# 05_CPU03.net
KiCad netlist of a schematic drawn in Altium Designer
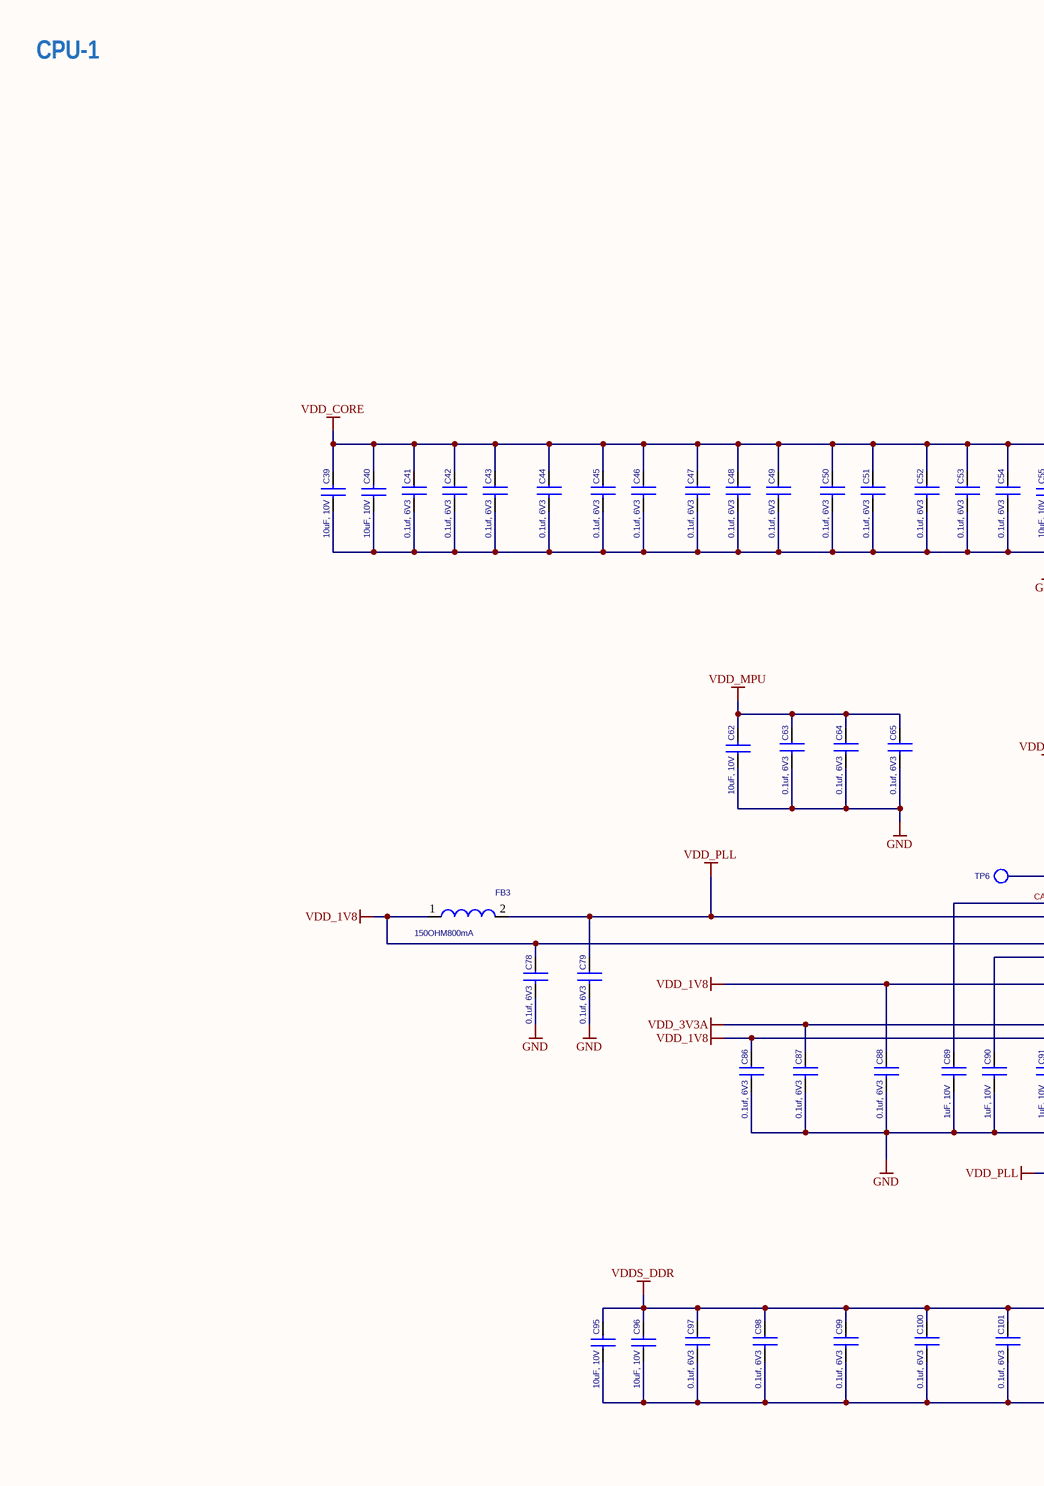
[diagram p0: 05_CPU03.SchDoc, left]
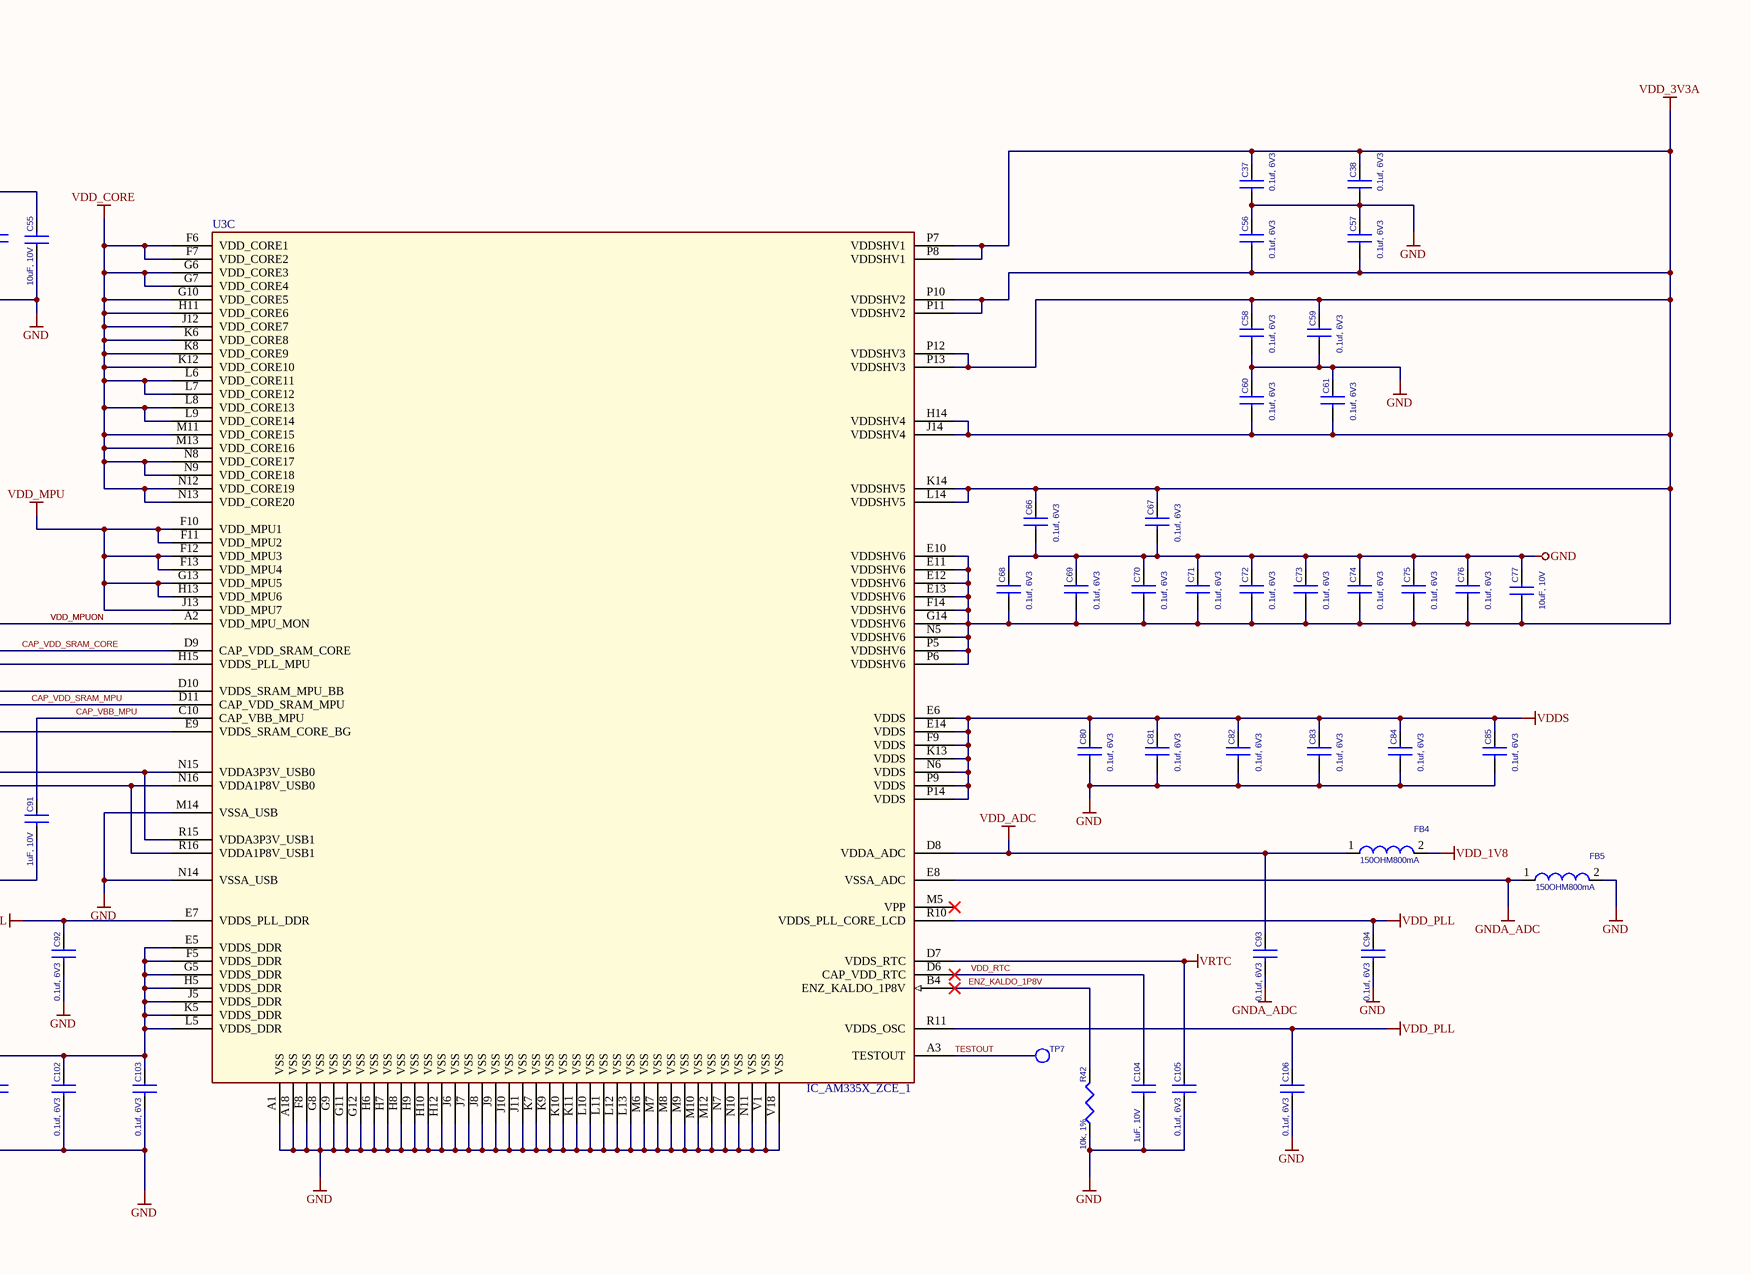
[diagram p1: 05_CPU03.SchDoc, right]

(export (version "E")
  (design (tool "Eeschema 10.0.6"))
  (components
    (comp (ref "C37")
      (value "0.1uf, 6V3")
      (footprint "402")
      (description "CAP CER 0.1UF 6.3V 10% X5R 0402")
      (fields
        (field (name "MANUFACTURER") "TDK Corporation")
        (field (name "MANUFACTURER PART NUMBER") "C1005X5R0J104K050BA")
      )
      (libsource (lib "BEAGLEBONEBLACK_REV A5B") (part "CAP_0.1uF_X7R_16V_10% 0402"))
    )
    (comp (ref "C38")
      (value "0.1uf, 6V3")
      (footprint "402")
      (description "CAP CER 0.1UF 6.3V 10% X5R 0402")
      (fields
        (field (name "MANUFACTURER") "TDK Corporation")
        (field (name "MANUFACTURER PART NUMBER") "C1005X5R0J104K050BA")
      )
      (libsource (lib "BEAGLEBONEBLACK_REV A5B") (part "CAP_0.1uF_X7R_16V_10% 0402"))
    )
    (comp (ref "C39")
      (value "10uF, 10V")
      (description "CAP CER 10UF 10V Y5V 0805")
      (fields
        (field (name "MANUFACTURER") "TDK Corporation")
        (field (name "MANUFACTURER PART NUMBER") "C2012Y5V1A106Z")
      )
      (libsource (lib "BEAGLEBONEBLACK_REV A5B") (part "CAP_10uF_Y5V_10V_10%_0805"))
    )
    (comp (ref "C40")
      (value "10uF, 10V")
      (description "CAP CER 10UF 10V Y5V 0805")
      (fields
        (field (name "MANUFACTURER") "TDK Corporation")
        (field (name "MANUFACTURER PART NUMBER") "C2012Y5V1A106Z")
      )
      (libsource (lib "BEAGLEBONEBLACK_REV A5B") (part "CAP_10uF_Y5V_10V_10%_0805"))
    )
    (comp (ref "C41")
      (value "0.1uf, 6V3")
      (footprint "402")
      (description "CAP CER 0.1UF 6.3V 10% X5R 0402")
      (fields
        (field (name "MANUFACTURER") "TDK Corporation")
        (field (name "MANUFACTURER PART NUMBER") "C1005X5R0J104K050BA")
      )
      (libsource (lib "BEAGLEBONEBLACK_REV A5B") (part "CAP_0.1uF_X7R_16V_10% 0402"))
    )
    (comp (ref "C42")
      (value "0.1uf, 6V3")
      (footprint "402")
      (description "CAP CER 0.1UF 6.3V 10% X5R 0402")
      (fields
        (field (name "MANUFACTURER") "TDK Corporation")
        (field (name "MANUFACTURER PART NUMBER") "C1005X5R0J104K050BA")
      )
      (libsource (lib "BEAGLEBONEBLACK_REV A5B") (part "CAP_0.1uF_X7R_16V_10% 0402"))
    )
    (comp (ref "C43")
      (value "0.1uf, 6V3")
      (footprint "402")
      (description "CAP CER 0.1UF 6.3V 10% X5R 0402")
      (fields
        (field (name "MANUFACTURER") "TDK Corporation")
        (field (name "MANUFACTURER PART NUMBER") "C1005X5R0J104K050BA")
      )
      (libsource (lib "BEAGLEBONEBLACK_REV A5B") (part "CAP_0.1uF_X7R_16V_10% 0402"))
    )
    (comp (ref "C44")
      (value "0.1uf, 6V3")
      (footprint "402")
      (description "CAP CER 0.1UF 6.3V 10% X5R 0402")
      (fields
        (field (name "MANUFACTURER") "TDK Corporation")
        (field (name "MANUFACTURER PART NUMBER") "C1005X5R0J104K050BA")
      )
      (libsource (lib "BEAGLEBONEBLACK_REV A5B") (part "CAP_0.1uF_X7R_16V_10% 0402"))
    )
    (comp (ref "C45")
      (value "0.1uf, 6V3")
      (footprint "402")
      (description "CAP CER 0.1UF 6.3V 10% X5R 0402")
      (fields
        (field (name "MANUFACTURER") "TDK Corporation")
        (field (name "MANUFACTURER PART NUMBER") "C1005X5R0J104K050BA")
      )
      (libsource (lib "BEAGLEBONEBLACK_REV A5B") (part "CAP_0.1uF_X7R_16V_10% 0402"))
    )
    (comp (ref "C46")
      (value "0.1uf, 6V3")
      (footprint "402")
      (description "CAP CER 0.1UF 6.3V 10% X5R 0402")
      (fields
        (field (name "MANUFACTURER") "TDK Corporation")
        (field (name "MANUFACTURER PART NUMBER") "C1005X5R0J104K050BA")
      )
      (libsource (lib "BEAGLEBONEBLACK_REV A5B") (part "CAP_0.1uF_X7R_16V_10% 0402"))
    )
    (comp (ref "C47")
      (value "0.1uf, 6V3")
      (footprint "402")
      (description "CAP CER 0.1UF 6.3V 10% X5R 0402")
      (fields
        (field (name "MANUFACTURER") "TDK Corporation")
        (field (name "MANUFACTURER PART NUMBER") "C1005X5R0J104K050BA")
      )
      (libsource (lib "BEAGLEBONEBLACK_REV A5B") (part "CAP_0.1uF_X7R_16V_10% 0402"))
    )
    (comp (ref "C48")
      (value "0.1uf, 6V3")
      (footprint "402")
      (description "CAP CER 0.1UF 6.3V 10% X5R 0402")
      (fields
        (field (name "MANUFACTURER") "TDK Corporation")
        (field (name "MANUFACTURER PART NUMBER") "C1005X5R0J104K050BA")
      )
      (libsource (lib "BEAGLEBONEBLACK_REV A5B") (part "CAP_0.1uF_X7R_16V_10% 0402"))
    )
    (comp (ref "C49")
      (value "0.1uf, 6V3")
      (footprint "402")
      (description "CAP CER 0.1UF 6.3V 10% X5R 0402")
      (fields
        (field (name "MANUFACTURER") "TDK Corporation")
        (field (name "MANUFACTURER PART NUMBER") "C1005X5R0J104K050BA")
      )
      (libsource (lib "BEAGLEBONEBLACK_REV A5B") (part "CAP_0.1uF_X7R_16V_10% 0402"))
    )
    (comp (ref "C50")
      (value "0.1uf, 6V3")
      (footprint "402")
      (description "CAP CER 0.1UF 6.3V 10% X5R 0402")
      (fields
        (field (name "MANUFACTURER") "TDK Corporation")
        (field (name "MANUFACTURER PART NUMBER") "C1005X5R0J104K050BA")
      )
      (libsource (lib "BEAGLEBONEBLACK_REV A5B") (part "CAP_0.1uF_X7R_16V_10% 0402"))
    )
    (comp (ref "C51")
      (value "0.1uf, 6V3")
      (footprint "402")
      (description "CAP CER 0.1UF 6.3V 10% X5R 0402")
      (fields
        (field (name "MANUFACTURER") "TDK Corporation")
        (field (name "MANUFACTURER PART NUMBER") "C1005X5R0J104K050BA")
      )
      (libsource (lib "BEAGLEBONEBLACK_REV A5B") (part "CAP_0.1uF_X7R_16V_10% 0402"))
    )
    (comp (ref "C52")
      (value "0.1uf, 6V3")
      (footprint "402")
      (description "CAP CER 0.1UF 6.3V 10% X5R 0402")
      (fields
        (field (name "MANUFACTURER") "TDK Corporation")
        (field (name "MANUFACTURER PART NUMBER") "C1005X5R0J104K050BA")
      )
      (libsource (lib "BEAGLEBONEBLACK_REV A5B") (part "CAP_0.1uF_X7R_16V_10% 0402"))
    )
    (comp (ref "C53")
      (value "0.1uf, 6V3")
      (footprint "402")
      (description "CAP CER 0.1UF 6.3V 10% X5R 0402")
      (fields
        (field (name "MANUFACTURER") "TDK Corporation")
        (field (name "MANUFACTURER PART NUMBER") "C1005X5R0J104K050BA")
      )
      (libsource (lib "BEAGLEBONEBLACK_REV A5B") (part "CAP_0.1uF_X7R_16V_10% 0402"))
    )
    (comp (ref "C54")
      (value "0.1uf, 6V3")
      (footprint "402")
      (description "CAP CER 0.1UF 6.3V 10% X5R 0402")
      (fields
        (field (name "MANUFACTURER") "TDK Corporation")
        (field (name "MANUFACTURER PART NUMBER") "C1005X5R0J104K050BA")
      )
      (libsource (lib "BEAGLEBONEBLACK_REV A5B") (part "CAP_0.1uF_X7R_16V_10% 0402"))
    )
    (comp (ref "C55")
      (value "10uF, 10V")
      (description "CAP CER 10UF 10V Y5V 0805")
      (fields
        (field (name "MANUFACTURER") "TDK Corporation")
        (field (name "MANUFACTURER PART NUMBER") "C2012Y5V1A106Z")
      )
      (libsource (lib "BEAGLEBONEBLACK_REV A5B") (part "CAP_10uF_Y5V_10V_10%_0805"))
    )
    (comp (ref "C56")
      (value "0.1uf, 6V3")
      (footprint "402")
      (description "CAP CER 0.1UF 6.3V 10% X5R 0402")
      (fields
        (field (name "MANUFACTURER") "TDK Corporation")
        (field (name "MANUFACTURER PART NUMBER") "C1005X5R0J104K050BA")
      )
      (libsource (lib "BEAGLEBONEBLACK_REV A5B") (part "CAP_0.1uF_X7R_16V_10% 0402"))
    )
    (comp (ref "C57")
      (value "0.1uf, 6V3")
      (footprint "402")
      (description "CAP CER 0.1UF 6.3V 10% X5R 0402")
      (fields
        (field (name "MANUFACTURER") "TDK Corporation")
        (field (name "MANUFACTURER PART NUMBER") "C1005X5R0J104K050BA")
      )
      (libsource (lib "BEAGLEBONEBLACK_REV A5B") (part "CAP_0.1uF_X7R_16V_10% 0402"))
    )
    (comp (ref "C58")
      (value "0.1uf, 6V3")
      (footprint "402")
      (description "CAP CER 0.1UF 6.3V 10% X5R 0402")
      (fields
        (field (name "MANUFACTURER") "TDK Corporation")
        (field (name "MANUFACTURER PART NUMBER") "C1005X5R0J104K050BA")
      )
      (libsource (lib "BEAGLEBONEBLACK_REV A5B") (part "CAP_0.1uF_X7R_16V_10% 0402"))
    )
    (comp (ref "C59")
      (value "0.1uf, 6V3")
      (footprint "402")
      (description "CAP CER 0.1UF 6.3V 10% X5R 0402")
      (fields
        (field (name "MANUFACTURER") "TDK Corporation")
        (field (name "MANUFACTURER PART NUMBER") "C1005X5R0J104K050BA")
      )
      (libsource (lib "BEAGLEBONEBLACK_REV A5B") (part "CAP_0.1uF_X7R_16V_10% 0402"))
    )
    (comp (ref "C60")
      (value "0.1uf, 6V3")
      (footprint "402")
      (description "CAP CER 0.1UF 6.3V 10% X5R 0402")
      (fields
        (field (name "MANUFACTURER") "TDK Corporation")
        (field (name "MANUFACTURER PART NUMBER") "C1005X5R0J104K050BA")
      )
      (libsource (lib "BEAGLEBONEBLACK_REV A5B") (part "CAP_0.1uF_X7R_16V_10% 0402"))
    )
    (comp (ref "C61")
      (value "0.1uf, 6V3")
      (footprint "402")
      (description "CAP CER 0.1UF 6.3V 10% X5R 0402")
      (fields
        (field (name "MANUFACTURER") "TDK Corporation")
        (field (name "MANUFACTURER PART NUMBER") "C1005X5R0J104K050BA")
      )
      (libsource (lib "BEAGLEBONEBLACK_REV A5B") (part "CAP_0.1uF_X7R_16V_10% 0402"))
    )
    (comp (ref "C62")
      (value "10uF, 10V")
      (description "CAP CER 10UF 10V Y5V 0805")
      (fields
        (field (name "MANUFACTURER") "TDK Corporation")
        (field (name "MANUFACTURER PART NUMBER") "C2012Y5V1A106Z")
      )
      (libsource (lib "BEAGLEBONEBLACK_REV A5B") (part "CAP_10uF_Y5V_10V_10%_0805"))
    )
    (comp (ref "C63")
      (value "0.1uf, 6V3")
      (footprint "402")
      (description "CAP CER 0.1UF 6.3V 10% X5R 0402")
      (fields
        (field (name "MANUFACTURER") "TDK Corporation")
        (field (name "MANUFACTURER PART NUMBER") "C1005X5R0J104K050BA")
      )
      (libsource (lib "BEAGLEBONEBLACK_REV A5B") (part "CAP_0.1uF_X7R_16V_10% 0402"))
    )
    (comp (ref "C64")
      (value "0.1uf, 6V3")
      (footprint "402")
      (description "CAP CER 0.1UF 6.3V 10% X5R 0402")
      (fields
        (field (name "MANUFACTURER") "TDK Corporation")
        (field (name "MANUFACTURER PART NUMBER") "C1005X5R0J104K050BA")
      )
      (libsource (lib "BEAGLEBONEBLACK_REV A5B") (part "CAP_0.1uF_X7R_16V_10% 0402"))
    )
    (comp (ref "C65")
      (value "0.1uf, 6V3")
      (footprint "402")
      (description "CAP CER 0.1UF 6.3V 10% X5R 0402")
      (fields
        (field (name "MANUFACTURER") "TDK Corporation")
        (field (name "MANUFACTURER PART NUMBER") "C1005X5R0J104K050BA")
      )
      (libsource (lib "BEAGLEBONEBLACK_REV A5B") (part "CAP_0.1uF_X7R_16V_10% 0402"))
    )
    (comp (ref "C66")
      (value "0.1uf, 6V3")
      (footprint "402")
      (description "CAP CER 0.1UF 6.3V 10% X5R 0402")
      (fields
        (field (name "MANUFACTURER") "TDK Corporation")
        (field (name "MANUFACTURER PART NUMBER") "C1005X5R0J104K050BA")
      )
      (libsource (lib "BEAGLEBONEBLACK_REV A5B") (part "CAP_0.1uF_X7R_16V_10% 0402"))
    )
    (comp (ref "C67")
      (value "0.1uf, 6V3")
      (footprint "402")
      (description "CAP CER 0.1UF 6.3V 10% X5R 0402")
      (fields
        (field (name "MANUFACTURER") "TDK Corporation")
        (field (name "MANUFACTURER PART NUMBER") "C1005X5R0J104K050BA")
      )
      (libsource (lib "BEAGLEBONEBLACK_REV A5B") (part "CAP_0.1uF_X7R_16V_10% 0402"))
    )
    (comp (ref "C68")
      (value "0.1uf, 6V3")
      (footprint "402")
      (description "CAP CER 0.1UF 6.3V 10% X5R 0402")
      (fields
        (field (name "MANUFACTURER") "TDK Corporation")
        (field (name "MANUFACTURER PART NUMBER") "C1005X5R0J104K050BA")
      )
      (libsource (lib "BEAGLEBONEBLACK_REV A5B") (part "CAP_0.1uF_X7R_16V_10% 0402"))
    )
    (comp (ref "C69")
      (value "0.1uf, 6V3")
      (footprint "402")
      (description "CAP CER 0.1UF 6.3V 10% X5R 0402")
      (fields
        (field (name "MANUFACTURER") "TDK Corporation")
        (field (name "MANUFACTURER PART NUMBER") "C1005X5R0J104K050BA")
      )
      (libsource (lib "BEAGLEBONEBLACK_REV A5B") (part "CAP_0.1uF_X7R_16V_10% 0402"))
    )
    (comp (ref "C70")
      (value "0.1uf, 6V3")
      (footprint "402")
      (description "CAP CER 0.1UF 6.3V 10% X5R 0402")
      (fields
        (field (name "MANUFACTURER") "TDK Corporation")
        (field (name "MANUFACTURER PART NUMBER") "C1005X5R0J104K050BA")
      )
      (libsource (lib "BEAGLEBONEBLACK_REV A5B") (part "CAP_0.1uF_X7R_16V_10% 0402"))
    )
    (comp (ref "C71")
      (value "0.1uf, 6V3")
      (footprint "402")
      (description "CAP CER 0.1UF 6.3V 10% X5R 0402")
      (fields
        (field (name "MANUFACTURER") "TDK Corporation")
        (field (name "MANUFACTURER PART NUMBER") "C1005X5R0J104K050BA")
      )
      (libsource (lib "BEAGLEBONEBLACK_REV A5B") (part "CAP_0.1uF_X7R_16V_10% 0402"))
    )
    (comp (ref "C72")
      (value "0.1uf, 6V3")
      (footprint "402")
      (description "CAP CER 0.1UF 6.3V 10% X5R 0402")
      (fields
        (field (name "MANUFACTURER") "TDK Corporation")
        (field (name "MANUFACTURER PART NUMBER") "C1005X5R0J104K050BA")
      )
      (libsource (lib "BEAGLEBONEBLACK_REV A5B") (part "CAP_0.1uF_X7R_16V_10% 0402"))
    )
    (comp (ref "C73")
      (value "0.1uf, 6V3")
      (footprint "402")
      (description "CAP CER 0.1UF 6.3V 10% X5R 0402")
      (fields
        (field (name "MANUFACTURER") "TDK Corporation")
        (field (name "MANUFACTURER PART NUMBER") "C1005X5R0J104K050BA")
      )
      (libsource (lib "BEAGLEBONEBLACK_REV A5B") (part "CAP_0.1uF_X7R_16V_10% 0402"))
    )
    (comp (ref "C74")
      (value "0.1uf, 6V3")
      (footprint "402")
      (description "CAP CER 0.1UF 6.3V 10% X5R 0402")
      (fields
        (field (name "MANUFACTURER") "TDK Corporation")
        (field (name "MANUFACTURER PART NUMBER") "C1005X5R0J104K050BA")
      )
      (libsource (lib "BEAGLEBONEBLACK_REV A5B") (part "CAP_0.1uF_X7R_16V_10% 0402"))
    )
    (comp (ref "C75")
      (value "0.1uf, 6V3")
      (footprint "402")
      (description "CAP CER 0.1UF 6.3V 10% X5R 0402")
      (fields
        (field (name "MANUFACTURER") "TDK Corporation")
        (field (name "MANUFACTURER PART NUMBER") "C1005X5R0J104K050BA")
      )
      (libsource (lib "BEAGLEBONEBLACK_REV A5B") (part "CAP_0.1uF_X7R_16V_10% 0402"))
    )
    (comp (ref "C76")
      (value "0.1uf, 6V3")
      (footprint "402")
      (description "CAP CER 0.1UF 6.3V 10% X5R 0402")
      (fields
        (field (name "MANUFACTURER") "TDK Corporation")
        (field (name "MANUFACTURER PART NUMBER") "C1005X5R0J104K050BA")
      )
      (libsource (lib "BEAGLEBONEBLACK_REV A5B") (part "CAP_0.1uF_X7R_16V_10% 0402"))
    )
    (comp (ref "C77")
      (value "10uF, 10V")
      (description "CAP CER 10UF 10V Y5V 0805")
      (fields
        (field (name "MANUFACTURER") "TDK Corporation")
        (field (name "MANUFACTURER PART NUMBER") "C2012Y5V1A106Z")
      )
      (libsource (lib "BEAGLEBONEBLACK_REV A5B") (part "CAP_10uF_Y5V_10V_10%_0805"))
    )
    (comp (ref "C78")
      (value "0.1uf, 6V3")
      (footprint "402")
      (description "CAP CER 0.1UF 6.3V 10% X5R 0402")
      (fields
        (field (name "MANUFACTURER") "TDK Corporation")
        (field (name "MANUFACTURER PART NUMBER") "C1005X5R0J104K050BA")
      )
      (libsource (lib "BEAGLEBONEBLACK_REV A5B") (part "CAP_0.1uF_X7R_16V_10% 0402"))
    )
    (comp (ref "C79")
      (value "0.1uf, 6V3")
      (footprint "402")
      (description "CAP CER 0.1UF 6.3V 10% X5R 0402")
      (fields
        (field (name "MANUFACTURER") "TDK Corporation")
        (field (name "MANUFACTURER PART NUMBER") "C1005X5R0J104K050BA")
      )
      (libsource (lib "BEAGLEBONEBLACK_REV A5B") (part "CAP_0.1uF_X7R_16V_10% 0402"))
    )
    (comp (ref "C80")
      (value "0.1uf, 6V3")
      (footprint "402")
      (description "CAP CER 0.1UF 6.3V 10% X5R 0402")
      (fields
        (field (name "MANUFACTURER") "TDK Corporation")
        (field (name "MANUFACTURER PART NUMBER") "C1005X5R0J104K050BA")
      )
      (libsource (lib "BEAGLEBONEBLACK_REV A5B") (part "CAP_0.1uF_X7R_16V_10% 0402"))
    )
    (comp (ref "C81")
      (value "0.1uf, 6V3")
      (footprint "402")
      (description "CAP CER 0.1UF 6.3V 10% X5R 0402")
      (fields
        (field (name "MANUFACTURER") "TDK Corporation")
        (field (name "MANUFACTURER PART NUMBER") "C1005X5R0J104K050BA")
      )
      (libsource (lib "BEAGLEBONEBLACK_REV A5B") (part "CAP_0.1uF_X7R_16V_10% 0402"))
    )
    (comp (ref "C82")
      (value "0.1uf, 6V3")
      (footprint "402")
      (description "CAP CER 0.1UF 6.3V 10% X5R 0402")
      (fields
        (field (name "MANUFACTURER") "TDK Corporation")
        (field (name "MANUFACTURER PART NUMBER") "C1005X5R0J104K050BA")
      )
      (libsource (lib "BEAGLEBONEBLACK_REV A5B") (part "CAP_0.1uF_X7R_16V_10% 0402"))
    )
    (comp (ref "C83")
      (value "0.1uf, 6V3")
      (footprint "402")
      (description "CAP CER 0.1UF 6.3V 10% X5R 0402")
      (fields
        (field (name "MANUFACTURER") "TDK Corporation")
        (field (name "MANUFACTURER PART NUMBER") "C1005X5R0J104K050BA")
      )
      (libsource (lib "BEAGLEBONEBLACK_REV A5B") (part "CAP_0.1uF_X7R_16V_10% 0402"))
    )
    (comp (ref "C84")
      (value "0.1uf, 6V3")
      (footprint "402")
      (description "CAP CER 0.1UF 6.3V 10% X5R 0402")
      (fields
        (field (name "MANUFACTURER") "TDK Corporation")
        (field (name "MANUFACTURER PART NUMBER") "C1005X5R0J104K050BA")
      )
      (libsource (lib "BEAGLEBONEBLACK_REV A5B") (part "CAP_0.1uF_X7R_16V_10% 0402"))
    )
    (comp (ref "C85")
      (value "0.1uf, 6V3")
      (footprint "402")
      (description "CAP CER 0.1UF 6.3V 10% X5R 0402")
      (fields
        (field (name "MANUFACTURER") "TDK Corporation")
        (field (name "MANUFACTURER PART NUMBER") "C1005X5R0J104K050BA")
      )
      (libsource (lib "BEAGLEBONEBLACK_REV A5B") (part "CAP_0.1uF_X7R_16V_10% 0402"))
    )
    (comp (ref "C86")
      (value "0.1uf, 6V3")
      (footprint "402")
      (description "CAP CER 0.1UF 6.3V 10% X5R 0402")
      (fields
        (field (name "MANUFACTURER") "TDK Corporation")
        (field (name "MANUFACTURER PART NUMBER") "C1005X5R0J104K050BA")
      )
      (libsource (lib "BEAGLEBONEBLACK_REV A5B") (part "CAP_0.1uF_X7R_16V_10% 0402"))
    )
    (comp (ref "C87")
      (value "0.1uf, 6V3")
      (footprint "402")
      (description "CAP CER 0.1UF 6.3V 10% X5R 0402")
      (fields
        (field (name "MANUFACTURER") "TDK Corporation")
        (field (name "MANUFACTURER PART NUMBER") "C1005X5R0J104K050BA")
      )
      (libsource (lib "BEAGLEBONEBLACK_REV A5B") (part "CAP_0.1uF_X7R_16V_10% 0402"))
    )
    (comp (ref "C88")
      (value "0.1uf, 6V3")
      (footprint "402")
      (description "CAP CER 0.1UF 6.3V 10% X5R 0402")
      (fields
        (field (name "MANUFACTURER") "TDK Corporation")
        (field (name "MANUFACTURER PART NUMBER") "C1005X5R0J104K050BA")
      )
      (libsource (lib "BEAGLEBONEBLACK_REV A5B") (part "CAP_0.1uF_X7R_16V_10% 0402"))
    )
    (comp (ref "C89")
      (value "1uF, 10V")
      (footprint "402")
      (description "CAP CER 1UF 10V 10% X5R 0402")
      (fields
        (field (name "MANUFACTURER") "AVX Corporation")
        (field (name "MANUFACTURER PART NUMBER") "0402ZD105KAT2A")
      )
      (libsource (lib "BEAGLEBONEBLACK_REV A5B") (part "CAP_1.0UF_X5R_10V_10%_0402"))
    )
    (comp (ref "C90")
      (value "1uF, 10V")
      (footprint "402")
      (description "CAP CER 1UF 10V 10% X5R 0402")
      (fields
        (field (name "MANUFACTURER") "AVX Corporation")
        (field (name "MANUFACTURER PART NUMBER") "0402ZD105KAT2A")
      )
      (libsource (lib "BEAGLEBONEBLACK_REV A5B") (part "CAP_1.0UF_X5R_10V_10%_0402"))
    )
    (comp (ref "C91")
      (value "1uF, 10V")
      (footprint "402")
      (description "CAP CER 1UF 10V 10% X5R 0402")
      (fields
        (field (name "MANUFACTURER") "AVX Corporation")
        (field (name "MANUFACTURER PART NUMBER") "0402ZD105KAT2A")
      )
      (libsource (lib "BEAGLEBONEBLACK_REV A5B") (part "CAP_1.0UF_X5R_10V_10%_0402"))
    )
    (comp (ref "C92")
      (value "0.1uf, 6V3")
      (footprint "402")
      (description "CAP CER 0.1UF 6.3V 10% X5R 0402")
      (fields
        (field (name "MANUFACTURER") "TDK Corporation")
        (field (name "MANUFACTURER PART NUMBER") "C1005X5R0J104K050BA")
      )
      (libsource (lib "BEAGLEBONEBLACK_REV A5B") (part "CAP_0.1uF_X7R_16V_10% 0402"))
    )
    (comp (ref "C93")
      (value "0.1uf, 6V3")
      (footprint "402")
      (description "CAP CER 0.1UF 6.3V 10% X5R 0402")
      (fields
        (field (name "MANUFACTURER") "TDK Corporation")
        (field (name "MANUFACTURER PART NUMBER") "C1005X5R0J104K050BA")
      )
      (libsource (lib "BEAGLEBONEBLACK_REV A5B") (part "CAP_0.1uF_X7R_16V_10% 0402"))
    )
    (comp (ref "C94")
      (value "0.1uf, 6V3")
      (footprint "402")
      (description "CAP CER 0.1UF 6.3V 10% X5R 0402")
      (fields
        (field (name "MANUFACTURER") "TDK Corporation")
        (field (name "MANUFACTURER PART NUMBER") "C1005X5R0J104K050BA")
      )
      (libsource (lib "BEAGLEBONEBLACK_REV A5B") (part "CAP_0.1uF_X7R_16V_10% 0402"))
    )
    (comp (ref "C95")
      (value "10uF, 10V")
      (description "CAP CER 10UF 10V Y5V 0805")
      (fields
        (field (name "MANUFACTURER") "TDK Corporation")
        (field (name "MANUFACTURER PART NUMBER") "C2012Y5V1A106Z")
      )
      (libsource (lib "BEAGLEBONEBLACK_REV A5B") (part "CAP_10uF_Y5V_10V_10%_0805"))
    )
    (comp (ref "C96")
      (value "10uF, 10V")
      (description "CAP CER 10UF 10V Y5V 0805")
      (fields
        (field (name "MANUFACTURER") "TDK Corporation")
        (field (name "MANUFACTURER PART NUMBER") "C2012Y5V1A106Z")
      )
      (libsource (lib "BEAGLEBONEBLACK_REV A5B") (part "CAP_10uF_Y5V_10V_10%_0805"))
    )
    (comp (ref "C97")
      (value "0.1uf, 6V3")
      (footprint "402")
      (description "CAP CER 0.1UF 6.3V 10% X5R 0402")
      (fields
        (field (name "MANUFACTURER") "TDK Corporation")
        (field (name "MANUFACTURER PART NUMBER") "C1005X5R0J104K050BA")
      )
      (libsource (lib "BEAGLEBONEBLACK_REV A5B") (part "CAP_0.1uF_X7R_16V_10% 0402"))
    )
    (comp (ref "C98")
      (value "0.1uf, 6V3")
      (footprint "402")
      (description "CAP CER 0.1UF 6.3V 10% X5R 0402")
      (fields
        (field (name "MANUFACTURER") "TDK Corporation")
        (field (name "MANUFACTURER PART NUMBER") "C1005X5R0J104K050BA")
      )
      (libsource (lib "BEAGLEBONEBLACK_REV A5B") (part "CAP_0.1uF_X7R_16V_10% 0402"))
    )
    (comp (ref "C99")
      (value "0.1uf, 6V3")
      (footprint "402")
      (description "CAP CER 0.1UF 6.3V 10% X5R 0402")
      (fields
        (field (name "MANUFACTURER") "TDK Corporation")
        (field (name "MANUFACTURER PART NUMBER") "C1005X5R0J104K050BA")
      )
      (libsource (lib "BEAGLEBONEBLACK_REV A5B") (part "CAP_0.1uF_X7R_16V_10% 0402"))
    )
    (comp (ref "C100")
      (value "0.1uf, 6V3")
      (footprint "402")
      (description "CAP CER 0.1UF 6.3V 10% X5R 0402")
      (fields
        (field (name "MANUFACTURER") "TDK Corporation")
        (field (name "MANUFACTURER PART NUMBER") "C1005X5R0J104K050BA")
      )
      (libsource (lib "BEAGLEBONEBLACK_REV A5B") (part "CAP_0.1uF_X7R_16V_10% 0402"))
    )
    (comp (ref "C101")
      (value "0.1uf, 6V3")
      (footprint "402")
      (description "CAP CER 0.1UF 6.3V 10% X5R 0402")
      (fields
        (field (name "MANUFACTURER") "TDK Corporation")
        (field (name "MANUFACTURER PART NUMBER") "C1005X5R0J104K050BA")
      )
      (libsource (lib "BEAGLEBONEBLACK_REV A5B") (part "CAP_0.1uF_X7R_16V_10% 0402"))
    )
    (comp (ref "C102")
      (value "0.1uf, 6V3")
      (footprint "402")
      (description "CAP CER 0.1UF 6.3V 10% X5R 0402")
      (fields
        (field (name "MANUFACTURER") "TDK Corporation")
        (field (name "MANUFACTURER PART NUMBER") "C1005X5R0J104K050BA")
      )
      (libsource (lib "BEAGLEBONEBLACK_REV A5B") (part "CAP_0.1uF_X7R_16V_10% 0402"))
    )
    (comp (ref "C103")
      (value "0.1uf, 6V3")
      (footprint "402")
      (description "CAP CER 0.1UF 6.3V 10% X5R 0402")
      (fields
        (field (name "MANUFACTURER") "TDK Corporation")
        (field (name "MANUFACTURER PART NUMBER") "C1005X5R0J104K050BA")
      )
      (libsource (lib "BEAGLEBONEBLACK_REV A5B") (part "CAP_0.1uF_X7R_16V_10% 0402"))
    )
    (comp (ref "C104")
      (value "1uF, 10V")
      (footprint "402")
      (description "CAP CER 1UF 10V 10% X5R 0402")
      (fields
        (field (name "MANUFACTURER") "AVX Corporation")
        (field (name "MANUFACTURER PART NUMBER") "0402ZD105KAT2A")
      )
      (libsource (lib "BEAGLEBONEBLACK_REV A5B") (part "CAP_1.0UF_X5R_10V_10%_0402"))
    )
    (comp (ref "C105")
      (value "0.1uf, 6V3")
      (footprint "402")
      (description "CAP CER 0.1UF 6.3V 10% X5R 0402")
      (fields
        (field (name "MANUFACTURER") "TDK Corporation")
        (field (name "MANUFACTURER PART NUMBER") "C1005X5R0J104K050BA")
      )
      (libsource (lib "BEAGLEBONEBLACK_REV A5B") (part "CAP_0.1uF_X7R_16V_10% 0402"))
    )
    (comp (ref "C106")
      (value "0.1uf, 6V3")
      (footprint "402")
      (description "CAP CER 0.1UF 6.3V 10% X5R 0402")
      (fields
        (field (name "MANUFACTURER") "TDK Corporation")
        (field (name "MANUFACTURER PART NUMBER") "C1005X5R0J104K050BA")
      )
      (libsource (lib "BEAGLEBONEBLACK_REV A5B") (part "CAP_0.1uF_X7R_16V_10% 0402"))
    )
    (comp (ref "FB3")
      (value "150OHM800mA")
      (footprint "SM-7351-IND-0805")
      (description "FERRITE 800MA 150 OHM 0805 SMD")
      (fields (field (name "MFR") "Steward") (field (name "TIINTPARTNUMBER") "1L0010"))
      (libsource (lib "BEAGLEBONEBLACK_REV A5B") (part "FER_180_200_0"))
    )
    (comp (ref "FB4")
      (value "150OHM800mA")
      (footprint "SM-7351-IND-0805")
      (description "FERRITE 800MA 150 OHM 0805 SMD")
      (fields (field (name "MFR") "Steward") (field (name "TIINTPARTNUMBER") "1L0010"))
      (libsource (lib "BEAGLEBONEBLACK_REV A5B") (part "FER_180_200_0"))
    )
    (comp (ref "FB5")
      (value "150OHM800mA")
      (footprint "SM-7351-IND-0805")
      (description "FERRITE 800MA 150 OHM 0805 SMD")
      (fields (field (name "MFR") "Steward") (field (name "TIINTPARTNUMBER") "1L0010"))
      (libsource (lib "BEAGLEBONEBLACK_REV A5B") (part "FER_180_200_0"))
    )
    (comp (ref "R42")
      (value "10k, 1%")
      (footprint "402")
      (description "RES 10K OHM 1/16W 5% 0402 SMD")
      (fields
        (field (name "MANUFACTURER") "Rohm Semiconductor")
        (field (name "MANUFACTURER PART NUMBER") "MCR01MZPJ103")
      )
      (libsource (lib "BEAGLEBONEBLACK_REV A5B") (part "RES_10K_1/16W_1%_0402"))
    )
    (comp (ref "TP6") (value "TESTPT1") (libsource (lib "BEAGLEBONEBLACK_REV A5B") (part "TESTPT1")))
    (comp (ref "TP7") (value "TESTPT1") (libsource (lib "BEAGLEBONEBLACK_REV A5B") (part "TESTPT1")))
    (comp (ref "U3")
      (value "IC_AM335X_ZCE_1")
      (footprint "am33xx_15x15")
      (description "SubArctic Cortex A8 Processor 15x15")
      (fields (field (name "MFR") "TI") (field (name "TIINTPARTNUMBER") "1A0242"))
      (libsource (lib "BEAGLEBONEBLACK_REV A5B") (part "IC_AM335X_ZCE_1"))
    )
  )
  (nets
    (net (code "1") (name "/CAP_VBB_MPU") (class "Default")
      (node (ref "C91") (pin "1") (pinfunction "1_1") (pintype "passive"))
      (node (ref "U3") (pin "C10") (pinfunction "CAP_VBB_MPU_C10") (pintype "passive"))
    )
    (net (code "2") (name "/CAP_VDD_SRAM_CORE") (class "Default")
      (node (ref "C89") (pin "1") (pinfunction "1_1") (pintype "passive"))
      (node (ref "U3") (pin "D9") (pinfunction "CAP_VDD_SRAM_CORE_D9") (pintype "power_in"))
    )
    (net (code "3") (name "/CAP_VDD_SRAM_MPU") (class "Default")
      (node (ref "C90") (pin "1") (pinfunction "1_1") (pintype "passive"))
      (node (ref "U3") (pin "D11") (pinfunction "CAP_VDD_SRAM_MPU_D11") (pintype "power_in"))
    )
    (net (code "4") (name "/ENZ_KALDO_1P8V") (class "Default")
      (node (ref "R42") (pin "2") (pinfunction "2_2") (pintype "passive"))
      (node (ref "U3") (pin "B4") (pinfunction "ENZ_KALDO_1P8V_B4") (pintype "input"))
    )
    (net (code "5") (name "/TESTOUT") (class "Default")
      (node (ref "TP7") (pin "1") (pinfunction "TP_1") (pintype "passive"))
      (node (ref "U3") (pin "A3") (pinfunction "TESTOUT_A3") (pintype "passive"))
    )
    (net (code "6") (name "/VDD_MPUON") (class "Default")
      (node (ref "TP6") (pin "1") (pinfunction "TP_1") (pintype "passive"))
      (node (ref "U3") (pin "A2") (pinfunction "VDD_MPU_MON_A2") (pintype "passive"))
    )
    (net (code "7") (name "/VDD_RTC") (class "Default")
      (node (ref "C104") (pin "1") (pinfunction "1_1") (pintype "passive"))
      (node (ref "U3") (pin "D6") (pinfunction "CAP_VDD_RTC_D6") (pintype "power_in"))
    )
    (net (code "8") (name "GND") (class "Default")
      (node (ref "C100") (pin "2") (pinfunction "2_2") (pintype "passive"))
      (node (ref "C101") (pin "2") (pinfunction "2_2") (pintype "passive"))
      (node (ref "C102") (pin "2") (pinfunction "2_2") (pintype "passive"))
      (node (ref "C103") (pin "2") (pinfunction "2_2") (pintype "passive"))
      (node (ref "C104") (pin "2") (pinfunction "2_2") (pintype "passive"))
      (node (ref "C105") (pin "2") (pinfunction "2_2") (pintype "passive"))
      (node (ref "C106") (pin "2") (pinfunction "2_2") (pintype "passive"))
      (node (ref "C37") (pin "2") (pinfunction "2_2") (pintype "passive"))
      (node (ref "C38") (pin "2") (pinfunction "2_2") (pintype "passive"))
      (node (ref "C39") (pin "1") (pinfunction "1_1") (pintype "passive"))
      (node (ref "C40") (pin "1") (pinfunction "1_1") (pintype "passive"))
      (node (ref "C41") (pin "2") (pinfunction "2_2") (pintype "passive"))
      (node (ref "C42") (pin "2") (pinfunction "2_2") (pintype "passive"))
      (node (ref "C43") (pin "2") (pinfunction "2_2") (pintype "passive"))
      (node (ref "C44") (pin "2") (pinfunction "2_2") (pintype "passive"))
      (node (ref "C45") (pin "2") (pinfunction "2_2") (pintype "passive"))
      (node (ref "C46") (pin "2") (pinfunction "2_2") (pintype "passive"))
      (node (ref "C47") (pin "2") (pinfunction "2_2") (pintype "passive"))
      (node (ref "C48") (pin "2") (pinfunction "2_2") (pintype "passive"))
      (node (ref "C49") (pin "2") (pinfunction "2_2") (pintype "passive"))
      (node (ref "C50") (pin "2") (pinfunction "2_2") (pintype "passive"))
      (node (ref "C51") (pin "2") (pinfunction "2_2") (pintype "passive"))
      (node (ref "C52") (pin "2") (pinfunction "2_2") (pintype "passive"))
      (node (ref "C53") (pin "2") (pinfunction "2_2") (pintype "passive"))
      (node (ref "C54") (pin "2") (pinfunction "2_2") (pintype "passive"))
      (node (ref "C55") (pin "1") (pinfunction "1_1") (pintype "passive"))
      (node (ref "C56") (pin "1") (pinfunction "1_1") (pintype "passive"))
      (node (ref "C57") (pin "1") (pinfunction "1_1") (pintype "passive"))
      (node (ref "C58") (pin "2") (pinfunction "2_2") (pintype "passive"))
      (node (ref "C59") (pin "2") (pinfunction "2_2") (pintype "passive"))
      (node (ref "C60") (pin "1") (pinfunction "1_1") (pintype "passive"))
      (node (ref "C61") (pin "1") (pinfunction "1_1") (pintype "passive"))
      (node (ref "C62") (pin "1") (pinfunction "1_1") (pintype "passive"))
      (node (ref "C63") (pin "2") (pinfunction "2_2") (pintype "passive"))
      (node (ref "C64") (pin "2") (pinfunction "2_2") (pintype "passive"))
      (node (ref "C65") (pin "2") (pinfunction "2_2") (pintype "passive"))
      (node (ref "C66") (pin "2") (pinfunction "2_2") (pintype "passive"))
      (node (ref "C67") (pin "2") (pinfunction "2_2") (pintype "passive"))
      (node (ref "C68") (pin "1") (pinfunction "1_1") (pintype "passive"))
      (node (ref "C69") (pin "1") (pinfunction "1_1") (pintype "passive"))
      (node (ref "C70") (pin "1") (pinfunction "1_1") (pintype "passive"))
      (node (ref "C71") (pin "1") (pinfunction "1_1") (pintype "passive"))
      (node (ref "C72") (pin "1") (pinfunction "1_1") (pintype "passive"))
      (node (ref "C73") (pin "1") (pinfunction "1_1") (pintype "passive"))
      (node (ref "C74") (pin "1") (pinfunction "1_1") (pintype "passive"))
      (node (ref "C75") (pin "1") (pinfunction "1_1") (pintype "passive"))
      (node (ref "C76") (pin "1") (pinfunction "1_1") (pintype "passive"))
      (node (ref "C77") (pin "2") (pinfunction "2_2") (pintype "passive"))
      (node (ref "C78") (pin "2") (pinfunction "2_2") (pintype "passive"))
      (node (ref "C79") (pin "2") (pinfunction "2_2") (pintype "passive"))
      (node (ref "C80") (pin "2") (pinfunction "2_2") (pintype "passive"))
      (node (ref "C81") (pin "2") (pinfunction "2_2") (pintype "passive"))
      (node (ref "C82") (pin "2") (pinfunction "2_2") (pintype "passive"))
      (node (ref "C83") (pin "2") (pinfunction "2_2") (pintype "passive"))
      (node (ref "C84") (pin "2") (pinfunction "2_2") (pintype "passive"))
      (node (ref "C85") (pin "2") (pinfunction "2_2") (pintype "passive"))
      (node (ref "C86") (pin "2") (pinfunction "2_2") (pintype "passive"))
      (node (ref "C87") (pin "2") (pinfunction "2_2") (pintype "passive"))
      (node (ref "C88") (pin "2") (pinfunction "2_2") (pintype "passive"))
      (node (ref "C89") (pin "2") (pinfunction "2_2") (pintype "passive"))
      (node (ref "C90") (pin "2") (pinfunction "2_2") (pintype "passive"))
      (node (ref "C91") (pin "2") (pinfunction "2_2") (pintype "passive"))
      (node (ref "C92") (pin "2") (pinfunction "2_2") (pintype "passive"))
      (node (ref "C94") (pin "2") (pinfunction "2_2") (pintype "passive"))
      (node (ref "C95") (pin "1") (pinfunction "1_1") (pintype "passive"))
      (node (ref "C96") (pin "1") (pinfunction "1_1") (pintype "passive"))
      (node (ref "C97") (pin "2") (pinfunction "2_2") (pintype "passive"))
      (node (ref "C98") (pin "2") (pinfunction "2_2") (pintype "passive"))
      (node (ref "C99") (pin "2") (pinfunction "2_2") (pintype "passive"))
      (node (ref "FB5") (pin "2") (pinfunction "2_2") (pintype "passive"))
      (node (ref "R42") (pin "1") (pinfunction "1_1") (pintype "passive"))
      (node (ref "U3") (pin "A1") (pinfunction "VSS_A1") (pintype "power_in"))
      (node (ref "U3") (pin "A18") (pinfunction "VSS_A18") (pintype "power_in"))
      (node (ref "U3") (pin "F8") (pinfunction "VSS_F8") (pintype "power_in"))
      (node (ref "U3") (pin "G11") (pinfunction "VSS_G11") (pintype "power_in"))
      (node (ref "U3") (pin "G12") (pinfunction "VSS_G12") (pintype "power_in"))
      (node (ref "U3") (pin "G8") (pinfunction "VSS_G8") (pintype "power_in"))
      (node (ref "U3") (pin "G9") (pinfunction "VSS_G9") (pintype "power_in"))
      (node (ref "U3") (pin "H10") (pinfunction "VSS_H10") (pintype "power_in"))
      (node (ref "U3") (pin "H12") (pinfunction "VSS_H12") (pintype "power_in"))
      (node (ref "U3") (pin "H6") (pinfunction "VSS_H6") (pintype "power_in"))
      (node (ref "U3") (pin "H7") (pinfunction "VSS_H7") (pintype "power_in"))
      (node (ref "U3") (pin "H8") (pinfunction "VSS_H8") (pintype "power_in"))
      (node (ref "U3") (pin "H9") (pinfunction "VSS_H9") (pintype "power_in"))
      (node (ref "U3") (pin "J10") (pinfunction "VSS_J10") (pintype "power_in"))
      (node (ref "U3") (pin "J11") (pinfunction "VSS_J11") (pintype "power_in"))
      (node (ref "U3") (pin "J6") (pinfunction "VSS_J6") (pintype "power_in"))
      (node (ref "U3") (pin "J7") (pinfunction "VSS_J7") (pintype "power_in"))
      (node (ref "U3") (pin "J8") (pinfunction "VSS_J8") (pintype "power_in"))
      (node (ref "U3") (pin "J9") (pinfunction "VSS_J9") (pintype "power_in"))
      (node (ref "U3") (pin "K10") (pinfunction "VSS_K10") (pintype "power_in"))
      (node (ref "U3") (pin "K11") (pinfunction "VSS_K11") (pintype "power_in"))
      (node (ref "U3") (pin "K7") (pinfunction "VSS_K7") (pintype "power_in"))
      (node (ref "U3") (pin "K9") (pinfunction "VSS_K9") (pintype "power_in"))
      (node (ref "U3") (pin "L10") (pinfunction "VSS_L10") (pintype "power_in"))
      (node (ref "U3") (pin "L11") (pinfunction "VSS_L11") (pintype "power_in"))
      (node (ref "U3") (pin "L12") (pinfunction "VSS_L12") (pintype "power_in"))
      (node (ref "U3") (pin "L13") (pinfunction "VSS_L13") (pintype "power_in"))
      (node (ref "U3") (pin "M10") (pinfunction "VSS_M10") (pintype "power_in"))
      (node (ref "U3") (pin "M12") (pinfunction "VSS_M12") (pintype "power_in"))
      (node (ref "U3") (pin "M14") (pinfunction "VSSA_USB_M14") (pintype "power_in"))
      (node (ref "U3") (pin "M6") (pinfunction "VSS_M6") (pintype "power_in"))
      (node (ref "U3") (pin "M7") (pinfunction "VSS_M7") (pintype "power_in"))
      (node (ref "U3") (pin "M8") (pinfunction "VSS_M8") (pintype "power_in"))
      (node (ref "U3") (pin "M9") (pinfunction "VSS_M9") (pintype "power_in"))
      (node (ref "U3") (pin "N10") (pinfunction "VSS_N10") (pintype "power_in"))
      (node (ref "U3") (pin "N11") (pinfunction "VSS_N11") (pintype "power_in"))
      (node (ref "U3") (pin "N14") (pinfunction "VSSA_USB_N14") (pintype "power_in"))
      (node (ref "U3") (pin "N7") (pinfunction "VSS_N7") (pintype "power_in"))
      (node (ref "U3") (pin "V1") (pinfunction "VSS_V1") (pintype "power_in"))
      (node (ref "U3") (pin "V18") (pinfunction "VSS_V18") (pintype "power_in"))
    )
    (net (code "9") (name "GNDA_ADC") (class "Default")
      (node (ref "C93") (pin "2") (pinfunction "2_2") (pintype "passive"))
      (node (ref "FB5") (pin "1") (pinfunction "1_1") (pintype "passive"))
      (node (ref "U3") (pin "E8") (pinfunction "VSSA_ADC_E8") (pintype "power_in"))
    )
    (net (code "10") (name "VDDS") (class "Default")
      (node (ref "C80") (pin "1") (pinfunction "1_1") (pintype "passive"))
      (node (ref "C81") (pin "1") (pinfunction "1_1") (pintype "passive"))
      (node (ref "C82") (pin "1") (pinfunction "1_1") (pintype "passive"))
      (node (ref "C83") (pin "1") (pinfunction "1_1") (pintype "passive"))
      (node (ref "C84") (pin "1") (pinfunction "1_1") (pintype "passive"))
      (node (ref "C85") (pin "1") (pinfunction "1_1") (pintype "passive"))
      (node (ref "U3") (pin "E14") (pinfunction "VDDS_E14") (pintype "power_in"))
      (node (ref "U3") (pin "E6") (pinfunction "VDDS_E6") (pintype "power_in"))
      (node (ref "U3") (pin "F9") (pinfunction "VDDS_F9") (pintype "power_in"))
      (node (ref "U3") (pin "K13") (pinfunction "VDDS_K13") (pintype "power_in"))
      (node (ref "U3") (pin "N6") (pinfunction "VDDS_N6") (pintype "power_in"))
      (node (ref "U3") (pin "P14") (pinfunction "VDDS_P14") (pintype "power_in"))
      (node (ref "U3") (pin "P9") (pinfunction "VDDS_P9") (pintype "power_in"))
    )
    (net (code "11") (name "VDDS_DDR") (class "Default")
      (node (ref "C100") (pin "1") (pinfunction "1_1") (pintype "passive"))
      (node (ref "C101") (pin "1") (pinfunction "1_1") (pintype "passive"))
      (node (ref "C102") (pin "1") (pinfunction "1_1") (pintype "passive"))
      (node (ref "C103") (pin "1") (pinfunction "1_1") (pintype "passive"))
      (node (ref "C95") (pin "2") (pinfunction "2_2") (pintype "passive"))
      (node (ref "C96") (pin "2") (pinfunction "2_2") (pintype "passive"))
      (node (ref "C97") (pin "1") (pinfunction "1_1") (pintype "passive"))
      (node (ref "C98") (pin "1") (pinfunction "1_1") (pintype "passive"))
      (node (ref "C99") (pin "1") (pinfunction "1_1") (pintype "passive"))
      (node (ref "U3") (pin "E5") (pinfunction "VDDS_DDR_E5") (pintype "power_in"))
      (node (ref "U3") (pin "F5") (pinfunction "VDDS_DDR_F5") (pintype "power_in"))
      (node (ref "U3") (pin "G5") (pinfunction "VDDS_DDR_G5") (pintype "power_in"))
      (node (ref "U3") (pin "H5") (pinfunction "VDDS_DDR_H5") (pintype "power_in"))
      (node (ref "U3") (pin "J5") (pinfunction "VDDS_DDR_J5") (pintype "power_in"))
      (node (ref "U3") (pin "K5") (pinfunction "VDDS_DDR_K5") (pintype "power_in"))
      (node (ref "U3") (pin "L5") (pinfunction "VDDS_DDR_L5") (pintype "power_in"))
    )
    (net (code "12") (name "VDD_1V8") (class "Default")
      (node (ref "C78") (pin "1") (pinfunction "1_1") (pintype "passive"))
      (node (ref "C86") (pin "1") (pinfunction "1_1") (pintype "passive"))
      (node (ref "C88") (pin "1") (pinfunction "1_1") (pintype "passive"))
      (node (ref "FB3") (pin "1") (pinfunction "1_1") (pintype "passive"))
      (node (ref "FB4") (pin "2") (pinfunction "2_2") (pintype "passive"))
      (node (ref "U3") (pin "D10") (pinfunction "VDDS_SRAM_MPU_BB_D10") (pintype "power_in"))
      (node (ref "U3") (pin "E9") (pinfunction "VDDS_SRAM_CORE_BG_E9") (pintype "power_in"))
      (node (ref "U3") (pin "N16") (pinfunction "VDDA1P8V_USB0_N16") (pintype "power_in"))
      (node (ref "U3") (pin "R16") (pinfunction "VDDA1P8V_USB1_R16") (pintype "power_in"))
    )
    (net (code "13") (name "VDD_3V3A") (class "Default")
      (node (ref "C37") (pin "1") (pinfunction "1_1") (pintype "passive"))
      (node (ref "C38") (pin "1") (pinfunction "1_1") (pintype "passive"))
      (node (ref "C56") (pin "2") (pinfunction "2_2") (pintype "passive"))
      (node (ref "C57") (pin "2") (pinfunction "2_2") (pintype "passive"))
      (node (ref "C58") (pin "1") (pinfunction "1_1") (pintype "passive"))
      (node (ref "C59") (pin "1") (pinfunction "1_1") (pintype "passive"))
      (node (ref "C60") (pin "2") (pinfunction "2_2") (pintype "passive"))
      (node (ref "C61") (pin "2") (pinfunction "2_2") (pintype "passive"))
      (node (ref "C66") (pin "1") (pinfunction "1_1") (pintype "passive"))
      (node (ref "C67") (pin "1") (pinfunction "1_1") (pintype "passive"))
      (node (ref "C68") (pin "2") (pinfunction "2_2") (pintype "passive"))
      (node (ref "C69") (pin "2") (pinfunction "2_2") (pintype "passive"))
      (node (ref "C70") (pin "2") (pinfunction "2_2") (pintype "passive"))
      (node (ref "C71") (pin "2") (pinfunction "2_2") (pintype "passive"))
      (node (ref "C72") (pin "2") (pinfunction "2_2") (pintype "passive"))
      (node (ref "C73") (pin "2") (pinfunction "2_2") (pintype "passive"))
      (node (ref "C74") (pin "2") (pinfunction "2_2") (pintype "passive"))
      (node (ref "C75") (pin "2") (pinfunction "2_2") (pintype "passive"))
      (node (ref "C76") (pin "2") (pinfunction "2_2") (pintype "passive"))
      (node (ref "C77") (pin "1") (pinfunction "1_1") (pintype "passive"))
      (node (ref "C87") (pin "1") (pinfunction "1_1") (pintype "passive"))
      (node (ref "U3") (pin "E10") (pinfunction "VDDSHV6_E10") (pintype "power_in"))
      (node (ref "U3") (pin "E11") (pinfunction "VDDSHV6_E11") (pintype "power_in"))
      (node (ref "U3") (pin "E12") (pinfunction "VDDSHV6_E12") (pintype "power_in"))
      (node (ref "U3") (pin "E13") (pinfunction "VDDSHV6_E13") (pintype "power_in"))
      (node (ref "U3") (pin "F14") (pinfunction "VDDSHV6_F14") (pintype "power_in"))
      (node (ref "U3") (pin "G14") (pinfunction "VDDSHV6_G14") (pintype "power_in"))
      (node (ref "U3") (pin "H14") (pinfunction "VDDSHV4_H14") (pintype "power_in"))
      (node (ref "U3") (pin "J14") (pinfunction "VDDSHV4_J14") (pintype "power_in"))
      (node (ref "U3") (pin "K14") (pinfunction "VDDSHV5_K14") (pintype "power_in"))
      (node (ref "U3") (pin "L14") (pinfunction "VDDSHV5_L14") (pintype "power_in"))
      (node (ref "U3") (pin "N15") (pinfunction "VDDA3P3V_USB0_N15") (pintype "power_in"))
      (node (ref "U3") (pin "N5") (pinfunction "VDDSHV6_N5") (pintype "power_in"))
      (node (ref "U3") (pin "P10") (pinfunction "VDDSHV2_P10") (pintype "power_in"))
      (node (ref "U3") (pin "P11") (pinfunction "VDDSHV2_P11") (pintype "power_in"))
      (node (ref "U3") (pin "P12") (pinfunction "VDDSHV3_P12") (pintype "power_in"))
      (node (ref "U3") (pin "P13") (pinfunction "VDDSHV3_P13") (pintype "power_in"))
      (node (ref "U3") (pin "P5") (pinfunction "VDDSHV6_P5") (pintype "power_in"))
      (node (ref "U3") (pin "P6") (pinfunction "VDDSHV6_P6") (pintype "power_in"))
      (node (ref "U3") (pin "P7") (pinfunction "VDDSHV1_P7") (pintype "power_in"))
      (node (ref "U3") (pin "P8") (pinfunction "VDDSHV1_P8") (pintype "power_in"))
      (node (ref "U3") (pin "R15") (pinfunction "VDDA3P3V_USB1_R15") (pintype "power_in"))
    )
    (net (code "14") (name "VDD_ADC") (class "Default")
      (node (ref "C93") (pin "1") (pinfunction "1_1") (pintype "passive"))
      (node (ref "FB4") (pin "1") (pinfunction "1_1") (pintype "passive"))
      (node (ref "U3") (pin "D8") (pinfunction "VDDA_ADC_D8") (pintype "power_in"))
    )
    (net (code "15") (name "VDD_CORE") (class "Default")
      (node (ref "C39") (pin "2") (pinfunction "2_2") (pintype "passive"))
      (node (ref "C40") (pin "2") (pinfunction "2_2") (pintype "passive"))
      (node (ref "C41") (pin "1") (pinfunction "1_1") (pintype "passive"))
      (node (ref "C42") (pin "1") (pinfunction "1_1") (pintype "passive"))
      (node (ref "C43") (pin "1") (pinfunction "1_1") (pintype "passive"))
      (node (ref "C44") (pin "1") (pinfunction "1_1") (pintype "passive"))
      (node (ref "C45") (pin "1") (pinfunction "1_1") (pintype "passive"))
      (node (ref "C46") (pin "1") (pinfunction "1_1") (pintype "passive"))
      (node (ref "C47") (pin "1") (pinfunction "1_1") (pintype "passive"))
      (node (ref "C48") (pin "1") (pinfunction "1_1") (pintype "passive"))
      (node (ref "C49") (pin "1") (pinfunction "1_1") (pintype "passive"))
      (node (ref "C50") (pin "1") (pinfunction "1_1") (pintype "passive"))
      (node (ref "C51") (pin "1") (pinfunction "1_1") (pintype "passive"))
      (node (ref "C52") (pin "1") (pinfunction "1_1") (pintype "passive"))
      (node (ref "C53") (pin "1") (pinfunction "1_1") (pintype "passive"))
      (node (ref "C54") (pin "1") (pinfunction "1_1") (pintype "passive"))
      (node (ref "C55") (pin "2") (pinfunction "2_2") (pintype "passive"))
      (node (ref "U3") (pin "F6") (pinfunction "VDD_CORE1_F6") (pintype "power_in"))
      (node (ref "U3") (pin "F7") (pinfunction "VDD_CORE2_F7") (pintype "power_in"))
      (node (ref "U3") (pin "G10") (pinfunction "VDD_CORE5_G10") (pintype "power_in"))
      (node (ref "U3") (pin "G6") (pinfunction "VDD_CORE3_G6") (pintype "power_in"))
      (node (ref "U3") (pin "G7") (pinfunction "VDD_CORE4_G7") (pintype "power_in"))
      (node (ref "U3") (pin "H11") (pinfunction "VDD_CORE6_H11") (pintype "power_in"))
      (node (ref "U3") (pin "J12") (pinfunction "VDD_CORE7_J12") (pintype "power_in"))
      (node (ref "U3") (pin "K12") (pinfunction "VDD_CORE10_K12") (pintype "power_in"))
      (node (ref "U3") (pin "K6") (pinfunction "VDD_CORE8_K6") (pintype "power_in"))
      (node (ref "U3") (pin "K8") (pinfunction "VDD_CORE9_K8") (pintype "power_in"))
      (node (ref "U3") (pin "L6") (pinfunction "VDD_CORE11_L6") (pintype "power_in"))
      (node (ref "U3") (pin "L7") (pinfunction "VDD_CORE12_L7") (pintype "power_in"))
      (node (ref "U3") (pin "L8") (pinfunction "VDD_CORE13_L8") (pintype "power_in"))
      (node (ref "U3") (pin "L9") (pinfunction "VDD_CORE14_L9") (pintype "power_in"))
      (node (ref "U3") (pin "M11") (pinfunction "VDD_CORE15_M11") (pintype "power_in"))
      (node (ref "U3") (pin "M13") (pinfunction "VDD_CORE16_M13") (pintype "power_in"))
      (node (ref "U3") (pin "N12") (pinfunction "VDD_CORE19_N12") (pintype "power_in"))
      (node (ref "U3") (pin "N13") (pinfunction "VDD_CORE20_N13") (pintype "power_in"))
      (node (ref "U3") (pin "N8") (pinfunction "VDD_CORE17_N8") (pintype "power_in"))
      (node (ref "U3") (pin "N9") (pinfunction "VDD_CORE18_N9") (pintype "power_in"))
    )
    (net (code "16") (name "VDD_MPU") (class "Default")
      (node (ref "C62") (pin "2") (pinfunction "2_2") (pintype "passive"))
      (node (ref "C63") (pin "1") (pinfunction "1_1") (pintype "passive"))
      (node (ref "C64") (pin "1") (pinfunction "1_1") (pintype "passive"))
      (node (ref "C65") (pin "1") (pinfunction "1_1") (pintype "passive"))
      (node (ref "U3") (pin "F10") (pinfunction "VDD_MPU1_F10") (pintype "power_in"))
      (node (ref "U3") (pin "F11") (pinfunction "VDD_MPU2_F11") (pintype "power_in"))
      (node (ref "U3") (pin "F12") (pinfunction "VDD_MPU3_F12") (pintype "power_in"))
      (node (ref "U3") (pin "F13") (pinfunction "VDD_MPU4_F13") (pintype "power_in"))
      (node (ref "U3") (pin "G13") (pinfunction "VDD_MPU5_G13") (pintype "power_in"))
      (node (ref "U3") (pin "H13") (pinfunction "VDD_MPU6_H13") (pintype "power_in"))
      (node (ref "U3") (pin "J13") (pinfunction "VDD_MPU7_J13") (pintype "power_in"))
    )
    (net (code "17") (name "VDD_PLL") (class "Default")
      (node (ref "C106") (pin "1") (pinfunction "1_1") (pintype "passive"))
      (node (ref "C79") (pin "1") (pinfunction "1_1") (pintype "passive"))
      (node (ref "C92") (pin "1") (pinfunction "1_1") (pintype "passive"))
      (node (ref "C94") (pin "1") (pinfunction "1_1") (pintype "passive"))
      (node (ref "FB3") (pin "2") (pinfunction "2_2") (pintype "passive"))
      (node (ref "U3") (pin "E7") (pinfunction "VDDS_PLL_DDR_E7") (pintype "power_in"))
      (node (ref "U3") (pin "H15") (pinfunction "VDDS_PLL_MPU_H15") (pintype "power_in"))
      (node (ref "U3") (pin "R10") (pinfunction "VDDS_PLL_CORE_LCD_R10") (pintype "power_in"))
      (node (ref "U3") (pin "R11") (pinfunction "VDDS_OSC_R11") (pintype "power_in"))
    )
    (net (code "18") (name "VRTC") (class "Default")
      (node (ref "C105") (pin "1") (pinfunction "1_1") (pintype "passive"))
      (node (ref "U3") (pin "D7") (pinfunction "VDDS_RTC_D7") (pintype "power_in"))
    )
    (net (code "19") (name "unconnected-(U3C-VPP-PadM5)") (class "Default")
      (node (ref "U3") (pin "M5") (pinfunction "VPP_M5") (pintype "power_in+no_connect"))
    )
  )
)
